# main.net
KiCad netlist of a schematic drawn in Altium Designer
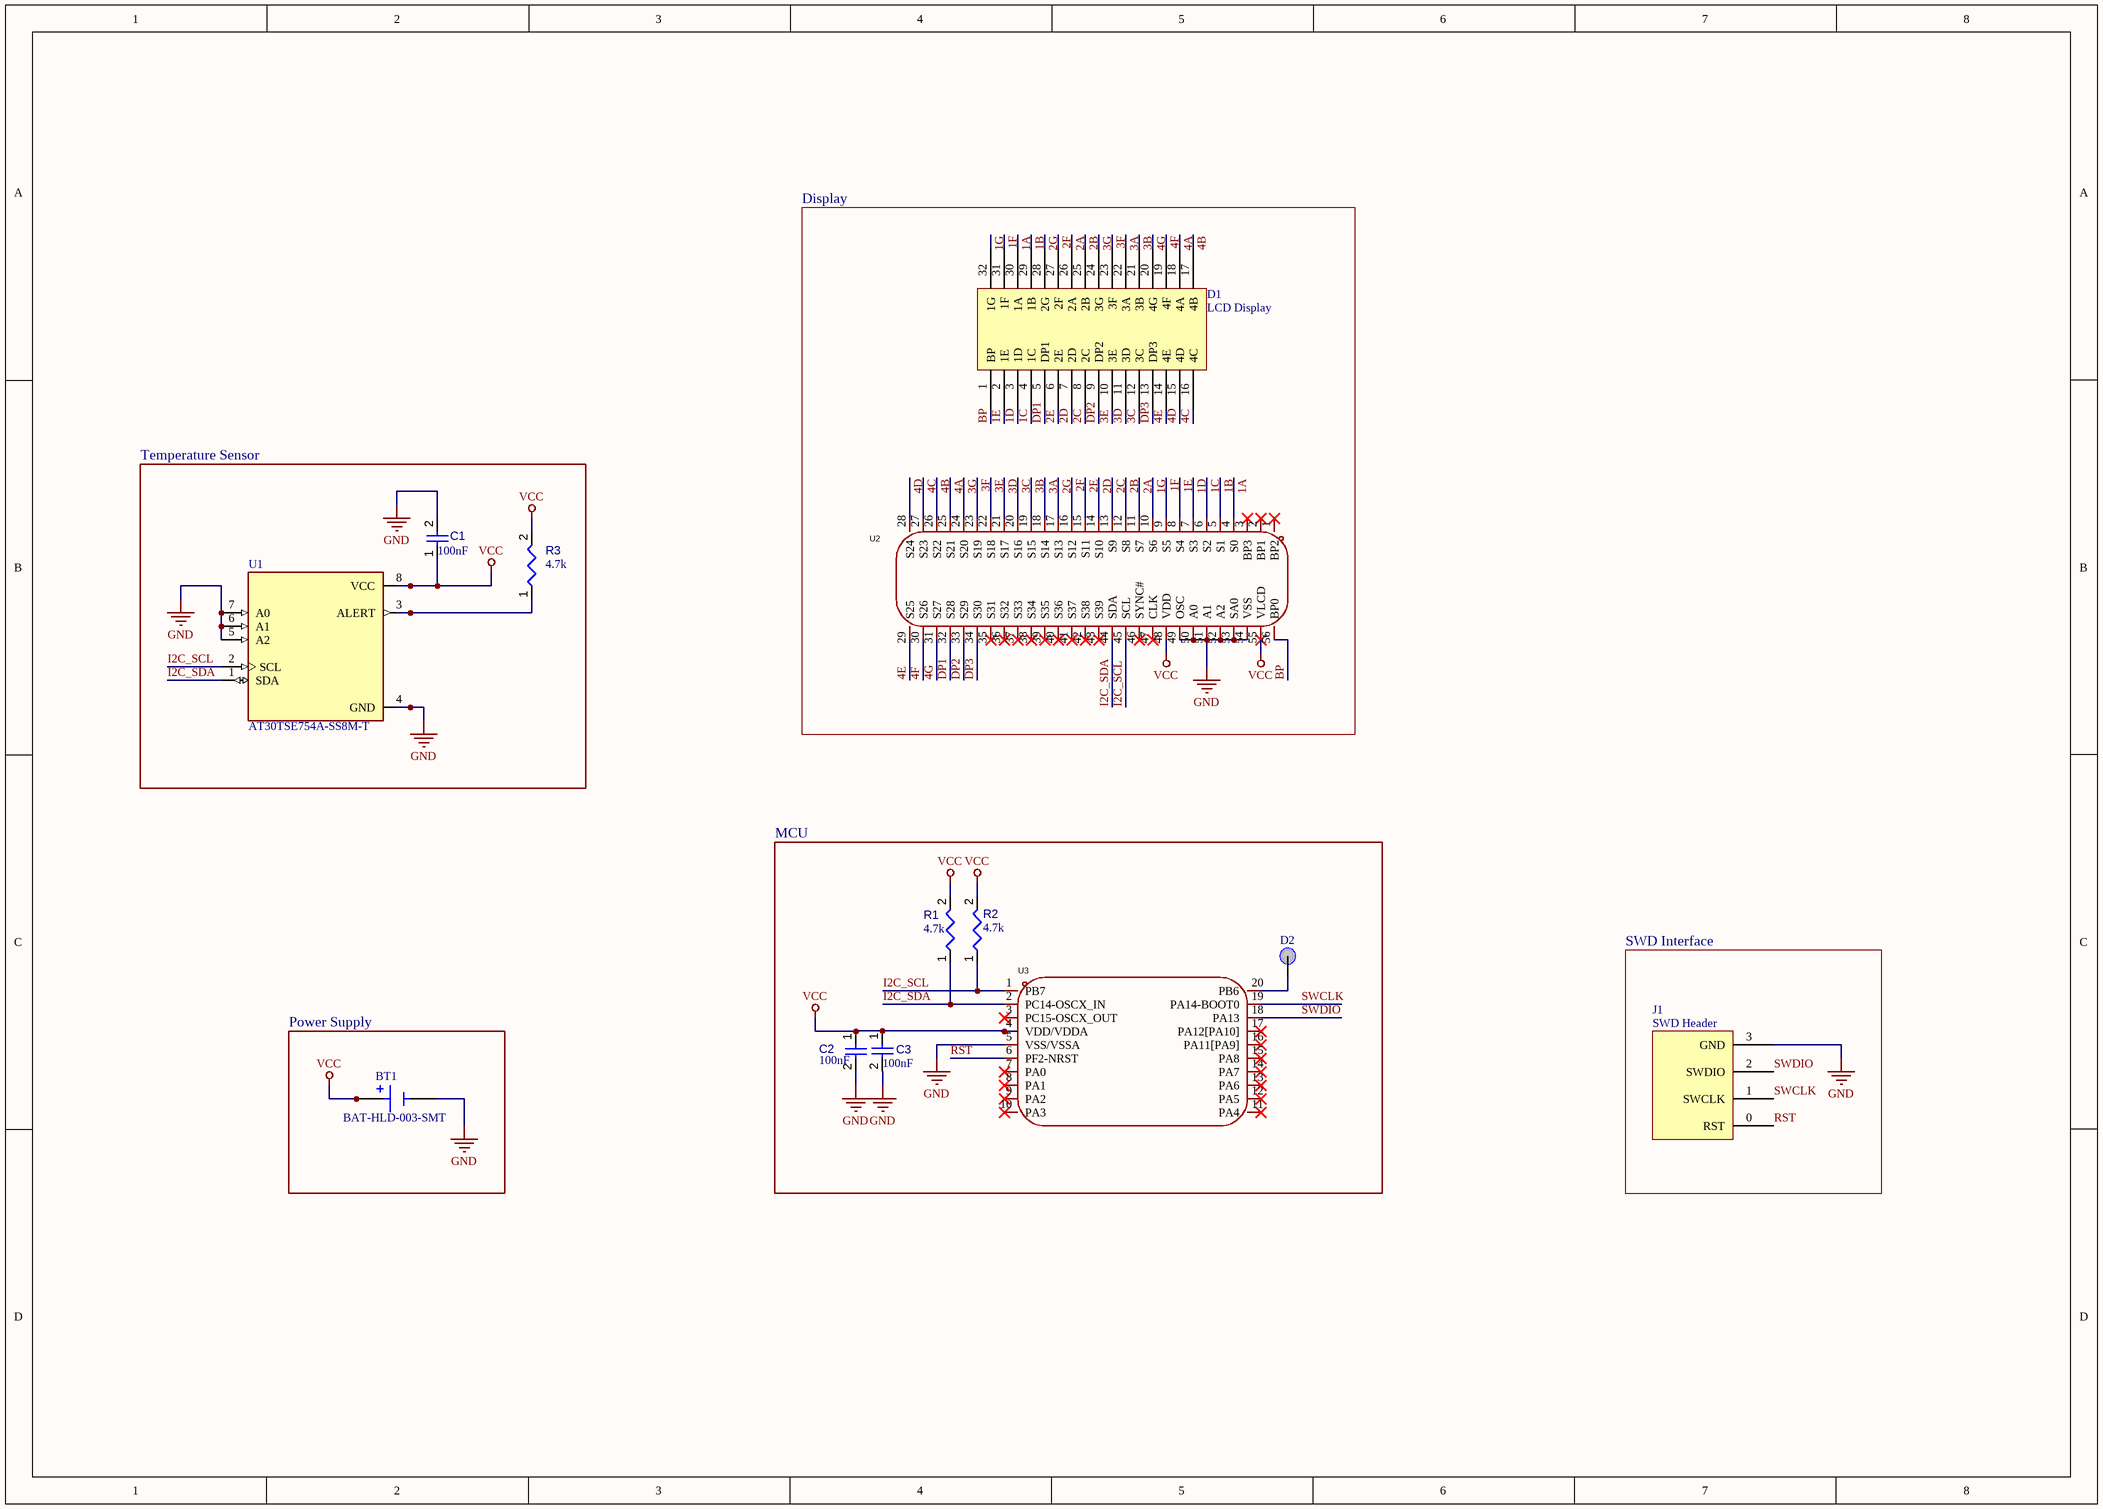
[diagram p0: main.SchDoc]

(export (version "E")
  (design (tool "Eeschema 10.0.6"))
  (components
    (comp (ref "BT1")
      (value "BAT-HLD-003-SMT")
      (footprint "BAT_BAT-HLD-003-SMT")
      (description "Battery Holder Coin 20 SMT Nickel")
      (fields (field (name "MF") "Linx Technologies Inc."))
      (libsource (lib "thermometer_lib") (part "BAT-HLD-003-SMT"))
    )
    (comp (ref "C1")
      (value "100nF")
      (footprint "CAPC2013X95X50LL10T25")
      (description "Chip Capacitor, 100 nF, +/- 10%, 50 V, 0805 (2012 Metric)")
      (fields (field (name "TOLERANCE") "10%") (field (name "Comment") "Capacitor 100 nF +/-10% 50 V 0805"))
      (libsource (lib "Learning") (part "CAP-NP-2"))
    )
    (comp (ref "C2")
      (value "100nF")
      (footprint "CAPC2013X95X50LL10T25")
      (description "Chip Capacitor, 100 nF, +/- 10%, 50 V, 0805 (2012 Metric)")
      (fields (field (name "TOLERANCE") "10%") (field (name "Comment") "Capacitor 100 nF +/-10% 50 V 0805"))
      (libsource (lib "Learning") (part "CAP-NP-2"))
    )
    (comp (ref "C3")
      (value "100nF")
      (footprint "CAPC2013X95X50LL10T25")
      (description "Chip Capacitor, 100 nF, +/- 10%, 50 V, 0805 (2012 Metric)")
      (fields (field (name "TOLERANCE") "10%") (field (name "Comment") "Capacitor 100 nF +/-10% 50 V 0805"))
      (libsource (lib "Learning") (part "CAP-NP-2"))
    )
    (comp (ref "D1")
      (value "LCD Display")
      (footprint "DE117RS2075V")
      (description "A 4 digit LCD Display with 4 Backplanes and no Backlight running at very low current (2uA/cm^2)")
      (libsource (lib "thermometer_lib") (part "DE117RS21"))
    )
    (comp (ref "D2")
      (value "Test Via")
      (footprint "Test Via")
      (description "Test via hole")
      (libsource (lib "thermometer_lib") (part "Test Via"))
    )
    (comp (ref "J1")
      (value "SWD Header")
      (footprint "4-Pin Header TH")
      (libsource (lib "thermometer_lib") (part "SWD Header"))
    )
    (comp (ref "R1")
      (value "4.7k")
      (footprint "RESC2013X70X40ML20T20")
      (description "Chip Resistor, 4.7 KOhm, +/- 1%, 0.125 W, -55 to 155 degC, 0805 (2012 Metric)")
      (fields (field (name "POWER") "125mW") (field (name "TOLERANCE") "1%"))
      (libsource (lib "Learning") (part "RES-2"))
    )
    (comp (ref "R2")
      (value "4.7k")
      (footprint "RESC2013X70X40ML20T20")
      (description "Chip Resistor, 4.7 KOhm, +/- 1%, 0.125 W, -55 to 155 degC, 0805 (2012 Metric)")
      (fields (field (name "POWER") "125mW") (field (name "TOLERANCE") "1%"))
      (libsource (lib "Learning") (part "RES-2"))
    )
    (comp (ref "R3")
      (value "4.7k")
      (footprint "RESC2013X70X40ML20T20")
      (description "Chip Resistor, 4.7 KOhm, +/- 1%, 0.125 W, -55 to 155 degC, 0805 (2012 Metric)")
      (fields (field (name "POWER") "125mW") (field (name "TOLERANCE") "1%"))
      (libsource (lib "Learning") (part "RES-2"))
    )
    (comp (ref "U1")
      (value "AT30TSE754A-SS8M-T")
      (footprint "SOIC127P599X175-8N")
      (description "Temperature Sensor")
      (libsource (lib "thermometer_lib") (part "AT30TSE754A-SS8M-T"))
    )
    (comp (ref "U2")
      (value "PCF85176T/1Y")
      (footprint "TSSOP-56_L14.0-W6.1-P0.50-LS8.1-BL")
      (description "40x4 Universal LCD Driver")
      (fields (field (name "MANUFACTURER") "NXP(恩智浦)"))
      (libsource (lib "thermometer_lib") (part "PCF85176T/1Y"))
    )
    (comp (ref "U3")
      (value "STM32C011F6P6")
      (footprint "TSSOP-20_L6.5-W4.4-P0.65-LS6.4-BL")
      (description "Microcontroller")
      (fields (field (name "MANUFACTURER") "ST(意法半导体)"))
      (libsource (lib "thermometer_lib") (part "STM32C011F6P6"))
    )
  )
  (nets
    (net (code "1") (name "/1A") (class "Default")
      (node (ref "D1") (pin "30") (pinfunction "1A_30") (pintype "passive"))
      (node (ref "U2") (pin "4") (pinfunction "S0_4") (pintype "passive"))
    )
    (net (code "2") (name "/1B") (class "Default")
      (node (ref "D1") (pin "29") (pinfunction "1B_29") (pintype "passive"))
      (node (ref "U2") (pin "5") (pinfunction "S1_5") (pintype "passive"))
    )
    (net (code "3") (name "/1C") (class "Default")
      (node (ref "D1") (pin "4") (pinfunction "1C_4") (pintype "passive"))
      (node (ref "U2") (pin "6") (pinfunction "S2_6") (pintype "passive"))
    )
    (net (code "4") (name "/1D") (class "Default")
      (node (ref "D1") (pin "3") (pinfunction "1D_3") (pintype "passive"))
      (node (ref "U2") (pin "7") (pinfunction "S3_7") (pintype "passive"))
    )
    (net (code "5") (name "/1E") (class "Default")
      (node (ref "D1") (pin "2") (pinfunction "1E_2") (pintype "passive"))
      (node (ref "U2") (pin "8") (pinfunction "S4_8") (pintype "passive"))
    )
    (net (code "6") (name "/1F") (class "Default")
      (node (ref "D1") (pin "31") (pinfunction "1F_31") (pintype "passive"))
      (node (ref "U2") (pin "9") (pinfunction "S5_9") (pintype "passive"))
    )
    (net (code "7") (name "/1G") (class "Default")
      (node (ref "D1") (pin "32") (pinfunction "1G_32") (pintype "passive"))
      (node (ref "U2") (pin "10") (pinfunction "S6_10") (pintype "passive"))
    )
    (net (code "8") (name "/2A") (class "Default")
      (node (ref "D1") (pin "26") (pinfunction "2A_26") (pintype "passive"))
      (node (ref "U2") (pin "11") (pinfunction "S7_11") (pintype "passive"))
    )
    (net (code "9") (name "/2B") (class "Default")
      (node (ref "D1") (pin "25") (pinfunction "2B_25") (pintype "passive"))
      (node (ref "U2") (pin "12") (pinfunction "S8_12") (pintype "passive"))
    )
    (net (code "10") (name "/2C") (class "Default")
      (node (ref "D1") (pin "8") (pinfunction "2C_8") (pintype "passive"))
      (node (ref "U2") (pin "13") (pinfunction "S9_13") (pintype "passive"))
    )
    (net (code "11") (name "/2D") (class "Default")
      (node (ref "D1") (pin "7") (pinfunction "2D_7") (pintype "passive"))
      (node (ref "U2") (pin "14") (pinfunction "S10_14") (pintype "passive"))
    )
    (net (code "12") (name "/2E") (class "Default")
      (node (ref "D1") (pin "6") (pinfunction "2E_6") (pintype "passive"))
      (node (ref "U2") (pin "15") (pinfunction "S11_15") (pintype "passive"))
    )
    (net (code "13") (name "/2F") (class "Default")
      (node (ref "D1") (pin "27") (pinfunction "2F_27") (pintype "passive"))
      (node (ref "U2") (pin "16") (pinfunction "S12_16") (pintype "passive"))
    )
    (net (code "14") (name "/2G") (class "Default")
      (node (ref "D1") (pin "28") (pinfunction "2G_28") (pintype "passive"))
      (node (ref "U2") (pin "17") (pinfunction "S13_17") (pintype "passive"))
    )
    (net (code "15") (name "/3A") (class "Default")
      (node (ref "D1") (pin "22") (pinfunction "3A_22") (pintype "passive"))
      (node (ref "U2") (pin "18") (pinfunction "S14_18") (pintype "passive"))
    )
    (net (code "16") (name "/3B") (class "Default")
      (node (ref "D1") (pin "21") (pinfunction "3B_21") (pintype "passive"))
      (node (ref "U2") (pin "19") (pinfunction "S15_19") (pintype "passive"))
    )
    (net (code "17") (name "/3C") (class "Default")
      (node (ref "D1") (pin "12") (pinfunction "3C_12") (pintype "passive"))
      (node (ref "U2") (pin "20") (pinfunction "S16_20") (pintype "passive"))
    )
    (net (code "18") (name "/3D") (class "Default")
      (node (ref "D1") (pin "11") (pinfunction "3D_11") (pintype "passive"))
      (node (ref "U2") (pin "21") (pinfunction "S17_21") (pintype "passive"))
    )
    (net (code "19") (name "/3E") (class "Default")
      (node (ref "D1") (pin "10") (pinfunction "3E_10") (pintype "passive"))
      (node (ref "U2") (pin "22") (pinfunction "S18_22") (pintype "passive"))
    )
    (net (code "20") (name "/3F") (class "Default")
      (node (ref "D1") (pin "23") (pinfunction "3F_23") (pintype "passive"))
      (node (ref "U2") (pin "23") (pinfunction "S19_23") (pintype "passive"))
    )
    (net (code "21") (name "/3G") (class "Default")
      (node (ref "D1") (pin "24") (pinfunction "3G_24") (pintype "passive"))
      (node (ref "U2") (pin "24") (pinfunction "S20_24") (pintype "passive"))
    )
    (net (code "22") (name "/4A") (class "Default")
      (node (ref "D1") (pin "18") (pinfunction "4A_18") (pintype "passive"))
      (node (ref "U2") (pin "25") (pinfunction "S21_25") (pintype "passive"))
    )
    (net (code "23") (name "/4B") (class "Default")
      (node (ref "D1") (pin "17") (pinfunction "4B_17") (pintype "passive"))
      (node (ref "U2") (pin "26") (pinfunction "S22_26") (pintype "passive"))
    )
    (net (code "24") (name "/4C") (class "Default")
      (node (ref "D1") (pin "16") (pinfunction "4C_16") (pintype "passive"))
      (node (ref "U2") (pin "27") (pinfunction "S23_27") (pintype "passive"))
    )
    (net (code "25") (name "/4D") (class "Default")
      (node (ref "D1") (pin "15") (pinfunction "4D_15") (pintype "passive"))
      (node (ref "U2") (pin "28") (pinfunction "S24_28") (pintype "passive"))
    )
    (net (code "26") (name "/4E") (class "Default")
      (node (ref "D1") (pin "14") (pinfunction "4E_14") (pintype "passive"))
      (node (ref "U2") (pin "29") (pinfunction "S25_29") (pintype "passive"))
    )
    (net (code "27") (name "/4F") (class "Default")
      (node (ref "D1") (pin "19") (pinfunction "4F_19") (pintype "passive"))
      (node (ref "U2") (pin "30") (pinfunction "S26_30") (pintype "passive"))
    )
    (net (code "28") (name "/4G") (class "Default")
      (node (ref "D1") (pin "20") (pinfunction "4G_20") (pintype "passive"))
      (node (ref "U2") (pin "31") (pinfunction "S27_31") (pintype "passive"))
    )
    (net (code "29") (name "/BP") (class "Default")
      (node (ref "D1") (pin "1") (pinfunction "BP_1") (pintype "passive"))
      (node (ref "U2") (pin "56") (pinfunction "BP0_56") (pintype "passive"))
    )
    (net (code "30") (name "/DP1") (class "Default")
      (node (ref "D1") (pin "5") (pinfunction "DP1_5") (pintype "passive"))
      (node (ref "U2") (pin "32") (pinfunction "S28_32") (pintype "passive"))
    )
    (net (code "31") (name "/DP2") (class "Default")
      (node (ref "D1") (pin "9") (pinfunction "DP2_9") (pintype "passive"))
      (node (ref "U2") (pin "33") (pinfunction "S29_33") (pintype "passive"))
    )
    (net (code "32") (name "/DP3") (class "Default")
      (node (ref "D1") (pin "13") (pinfunction "DP3_13") (pintype "passive"))
      (node (ref "U2") (pin "34") (pinfunction "S30_34") (pintype "passive"))
    )
    (net (code "33") (name "/I2C_SCL") (class "Default")
      (node (ref "R2") (pin "1") (pinfunction "1_1") (pintype "passive"))
      (node (ref "U1") (pin "2") (pinfunction "SCL_2") (pintype "input"))
      (node (ref "U2") (pin "45") (pinfunction "SCL_45") (pintype "passive"))
      (node (ref "U3") (pin "1") (pinfunction "PB7_1") (pintype "passive"))
    )
    (net (code "34") (name "/I2C_SDA") (class "Default")
      (node (ref "R1") (pin "1") (pinfunction "1_1") (pintype "passive"))
      (node (ref "U1") (pin "1") (pinfunction "SDA_1") (pintype "bidirectional"))
      (node (ref "U2") (pin "44") (pinfunction "SDA_44") (pintype "passive"))
      (node (ref "U3") (pin "2") (pinfunction "PC14-OSCX_IN_2") (pintype "passive"))
    )
    (net (code "35") (name "/RST") (class "Default")
      (node (ref "J1") (pin "0") (pinfunction "RST_0") (pintype "passive"))
      (node (ref "U3") (pin "6") (pinfunction "PF2-NRST_6") (pintype "passive"))
    )
    (net (code "36") (name "/SWCLK") (class "Default")
      (node (ref "J1") (pin "1") (pinfunction "SWCLK_1") (pintype "passive"))
      (node (ref "U3") (pin "19") (pinfunction "PA14-BOOT0_19") (pintype "passive"))
    )
    (net (code "37") (name "/SWDIO") (class "Default")
      (node (ref "J1") (pin "2") (pinfunction "SWDIO_2") (pintype "passive"))
      (node (ref "U3") (pin "18") (pinfunction "PA13_18") (pintype "passive"))
    )
    (net (code "38") (name "GND") (class "Default")
      (node (ref "BT1") (pin "N") (pinfunction "NEG_N") (pintype "passive"))
      (node (ref "C1") (pin "2") (pinfunction "2_2") (pintype "passive"))
      (node (ref "C2") (pin "2") (pinfunction "2_2") (pintype "passive"))
      (node (ref "C3") (pin "2") (pinfunction "2_2") (pintype "passive"))
      (node (ref "J1") (pin "3") (pinfunction "GND_3") (pintype "passive"))
      (node (ref "U1") (pin "4") (pinfunction "GND_4") (pintype "power_in"))
      (node (ref "U1") (pin "5") (pinfunction "A2_5") (pintype "input"))
      (node (ref "U1") (pin "6") (pinfunction "A1_6") (pintype "input"))
      (node (ref "U1") (pin "7") (pinfunction "A0_7") (pintype "input"))
      (node (ref "U2") (pin "49") (pinfunction "OSC_49") (pintype "passive"))
      (node (ref "U2") (pin "50") (pinfunction "A0_50") (pintype "passive"))
      (node (ref "U2") (pin "51") (pinfunction "A1_51") (pintype "passive"))
      (node (ref "U2") (pin "52") (pinfunction "A2_52") (pintype "passive"))
      (node (ref "U2") (pin "53") (pinfunction "SA0_53") (pintype "passive"))
      (node (ref "U2") (pin "54") (pinfunction "VSS_54") (pintype "passive"))
      (node (ref "U3") (pin "5") (pinfunction "VSS/VSSA_5") (pintype "passive"))
    )
    (net (code "39") (name "Net-(U1-ALERT)") (class "Default")
      (node (ref "R3") (pin "1") (pinfunction "1_1") (pintype "passive"))
      (node (ref "U1") (pin "3") (pinfunction "ALERT_3") (pintype "output"))
    )
    (net (code "40") (name "Net-(U3-PB6)") (class "Default")
      (node (ref "D2") (pin "1") (pinfunction "1_1") (pintype "passive"))
      (node (ref "U3") (pin "20") (pinfunction "PB6_20") (pintype "passive"))
    )
    (net (code "41") (name "VCC") (class "Default")
      (node (ref "BT1") (pin "P1") (pinfunction "POS_P1") (pintype "passive"))
      (node (ref "BT1") (pin "P2") (pinfunction "POS_P2") (pintype "passive"))
      (node (ref "C1") (pin "1") (pinfunction "1_1") (pintype "passive"))
      (node (ref "C2") (pin "1") (pinfunction "1_1") (pintype "passive"))
      (node (ref "C3") (pin "1") (pinfunction "1_1") (pintype "passive"))
      (node (ref "R1") (pin "2") (pinfunction "2_2") (pintype "passive"))
      (node (ref "R2") (pin "2") (pinfunction "2_2") (pintype "passive"))
      (node (ref "R3") (pin "2") (pinfunction "2_2") (pintype "passive"))
      (node (ref "U1") (pin "8") (pinfunction "VCC_8") (pintype "power_in"))
      (node (ref "U2") (pin "48") (pinfunction "VDD_48") (pintype "passive"))
      (node (ref "U2") (pin "55") (pinfunction "VLCD_55") (pintype "passive"))
      (node (ref "U3") (pin "4") (pinfunction "VDD/VDDA_4") (pintype "passive"))
    )
    (net (code "42") (name "unconnected-(U2-BP1-Pad2)") (class "Default")
      (node (ref "U2") (pin "2") (pinfunction "BP1_2") (pintype "passive+no_connect"))
    )
    (net (code "43") (name "unconnected-(U2-BP2-Pad1)") (class "Default")
      (node (ref "U2") (pin "1") (pinfunction "BP2_1") (pintype "passive+no_connect"))
    )
    (net (code "44") (name "unconnected-(U2-BP3-Pad3)") (class "Default")
      (node (ref "U2") (pin "3") (pinfunction "BP3_3") (pintype "passive+no_connect"))
    )
    (net (code "45") (name "unconnected-(U2-CLK-Pad47)") (class "Default")
      (node (ref "U2") (pin "47") (pinfunction "CLK_47") (pintype "passive+no_connect"))
    )
    (net (code "46") (name "unconnected-(U2-S31-Pad35)") (class "Default")
      (node (ref "U2") (pin "35") (pinfunction "S31_35") (pintype "passive+no_connect"))
    )
    (net (code "47") (name "unconnected-(U2-S32-Pad36)") (class "Default")
      (node (ref "U2") (pin "36") (pinfunction "S32_36") (pintype "passive+no_connect"))
    )
    (net (code "48") (name "unconnected-(U2-S33-Pad37)") (class "Default")
      (node (ref "U2") (pin "37") (pinfunction "S33_37") (pintype "passive+no_connect"))
    )
    (net (code "49") (name "unconnected-(U2-S34-Pad38)") (class "Default")
      (node (ref "U2") (pin "38") (pinfunction "S34_38") (pintype "passive+no_connect"))
    )
    (net (code "50") (name "unconnected-(U2-S35-Pad39)") (class "Default")
      (node (ref "U2") (pin "39") (pinfunction "S35_39") (pintype "passive+no_connect"))
    )
    (net (code "51") (name "unconnected-(U2-S36-Pad40)") (class "Default")
      (node (ref "U2") (pin "40") (pinfunction "S36_40") (pintype "passive+no_connect"))
    )
    (net (code "52") (name "unconnected-(U2-S37-Pad41)") (class "Default")
      (node (ref "U2") (pin "41") (pinfunction "S37_41") (pintype "passive+no_connect"))
    )
    (net (code "53") (name "unconnected-(U2-S38-Pad42)") (class "Default")
      (node (ref "U2") (pin "42") (pinfunction "S38_42") (pintype "passive+no_connect"))
    )
    (net (code "54") (name "unconnected-(U2-S39-Pad43)") (class "Default")
      (node (ref "U2") (pin "43") (pinfunction "S39_43") (pintype "passive+no_connect"))
    )
    (net (code "55") (name "unconnected-(U2-SYNC#-Pad46)") (class "Default")
      (node (ref "U2") (pin "46") (pinfunction "SYNC#_46") (pintype "passive+no_connect"))
    )
    (net (code "56") (name "unconnected-(U3-PA0-Pad7)") (class "Default")
      (node (ref "U3") (pin "7") (pinfunction "PA0_7") (pintype "passive+no_connect"))
    )
    (net (code "57") (name "unconnected-(U3-PA1-Pad8)") (class "Default")
      (node (ref "U3") (pin "8") (pinfunction "PA1_8") (pintype "passive+no_connect"))
    )
    (net (code "58") (name "unconnected-(U3-PA2-Pad9)") (class "Default")
      (node (ref "U3") (pin "9") (pinfunction "PA2_9") (pintype "passive+no_connect"))
    )
    (net (code "59") (name "unconnected-(U3-PA3-Pad10)") (class "Default")
      (node (ref "U3") (pin "10") (pinfunction "PA3_10") (pintype "passive+no_connect"))
    )
    (net (code "60") (name "unconnected-(U3-PA4-Pad11)") (class "Default")
      (node (ref "U3") (pin "11") (pinfunction "PA4_11") (pintype "passive+no_connect"))
    )
    (net (code "61") (name "unconnected-(U3-PA5-Pad12)") (class "Default")
      (node (ref "U3") (pin "12") (pinfunction "PA5_12") (pintype "passive+no_connect"))
    )
    (net (code "62") (name "unconnected-(U3-PA6-Pad13)") (class "Default")
      (node (ref "U3") (pin "13") (pinfunction "PA6_13") (pintype "passive+no_connect"))
    )
    (net (code "63") (name "unconnected-(U3-PA7-Pad14)") (class "Default")
      (node (ref "U3") (pin "14") (pinfunction "PA7_14") (pintype "passive+no_connect"))
    )
    (net (code "64") (name "unconnected-(U3-PA8-Pad15)") (class "Default")
      (node (ref "U3") (pin "15") (pinfunction "PA8_15") (pintype "passive+no_connect"))
    )
    (net (code "65") (name "unconnected-(U3-PA11[PA9]-Pad16)") (class "Default")
      (node (ref "U3") (pin "16") (pinfunction "PA11[PA9]_16") (pintype "passive+no_connect"))
    )
    (net (code "66") (name "unconnected-(U3-PA12[PA10]-Pad17)") (class "Default")
      (node (ref "U3") (pin "17") (pinfunction "PA12[PA10]_17") (pintype "passive+no_connect"))
    )
    (net (code "67") (name "unconnected-(U3-PC15-OSCX_OUT-Pad3)") (class "Default")
      (node (ref "U3") (pin "3") (pinfunction "PC15-OSCX_OUT_3") (pintype "passive+no_connect"))
    )
  )
)
